# ProDoc_v3.net
KiCad netlist of a schematic drawn in EasyEDA Pro
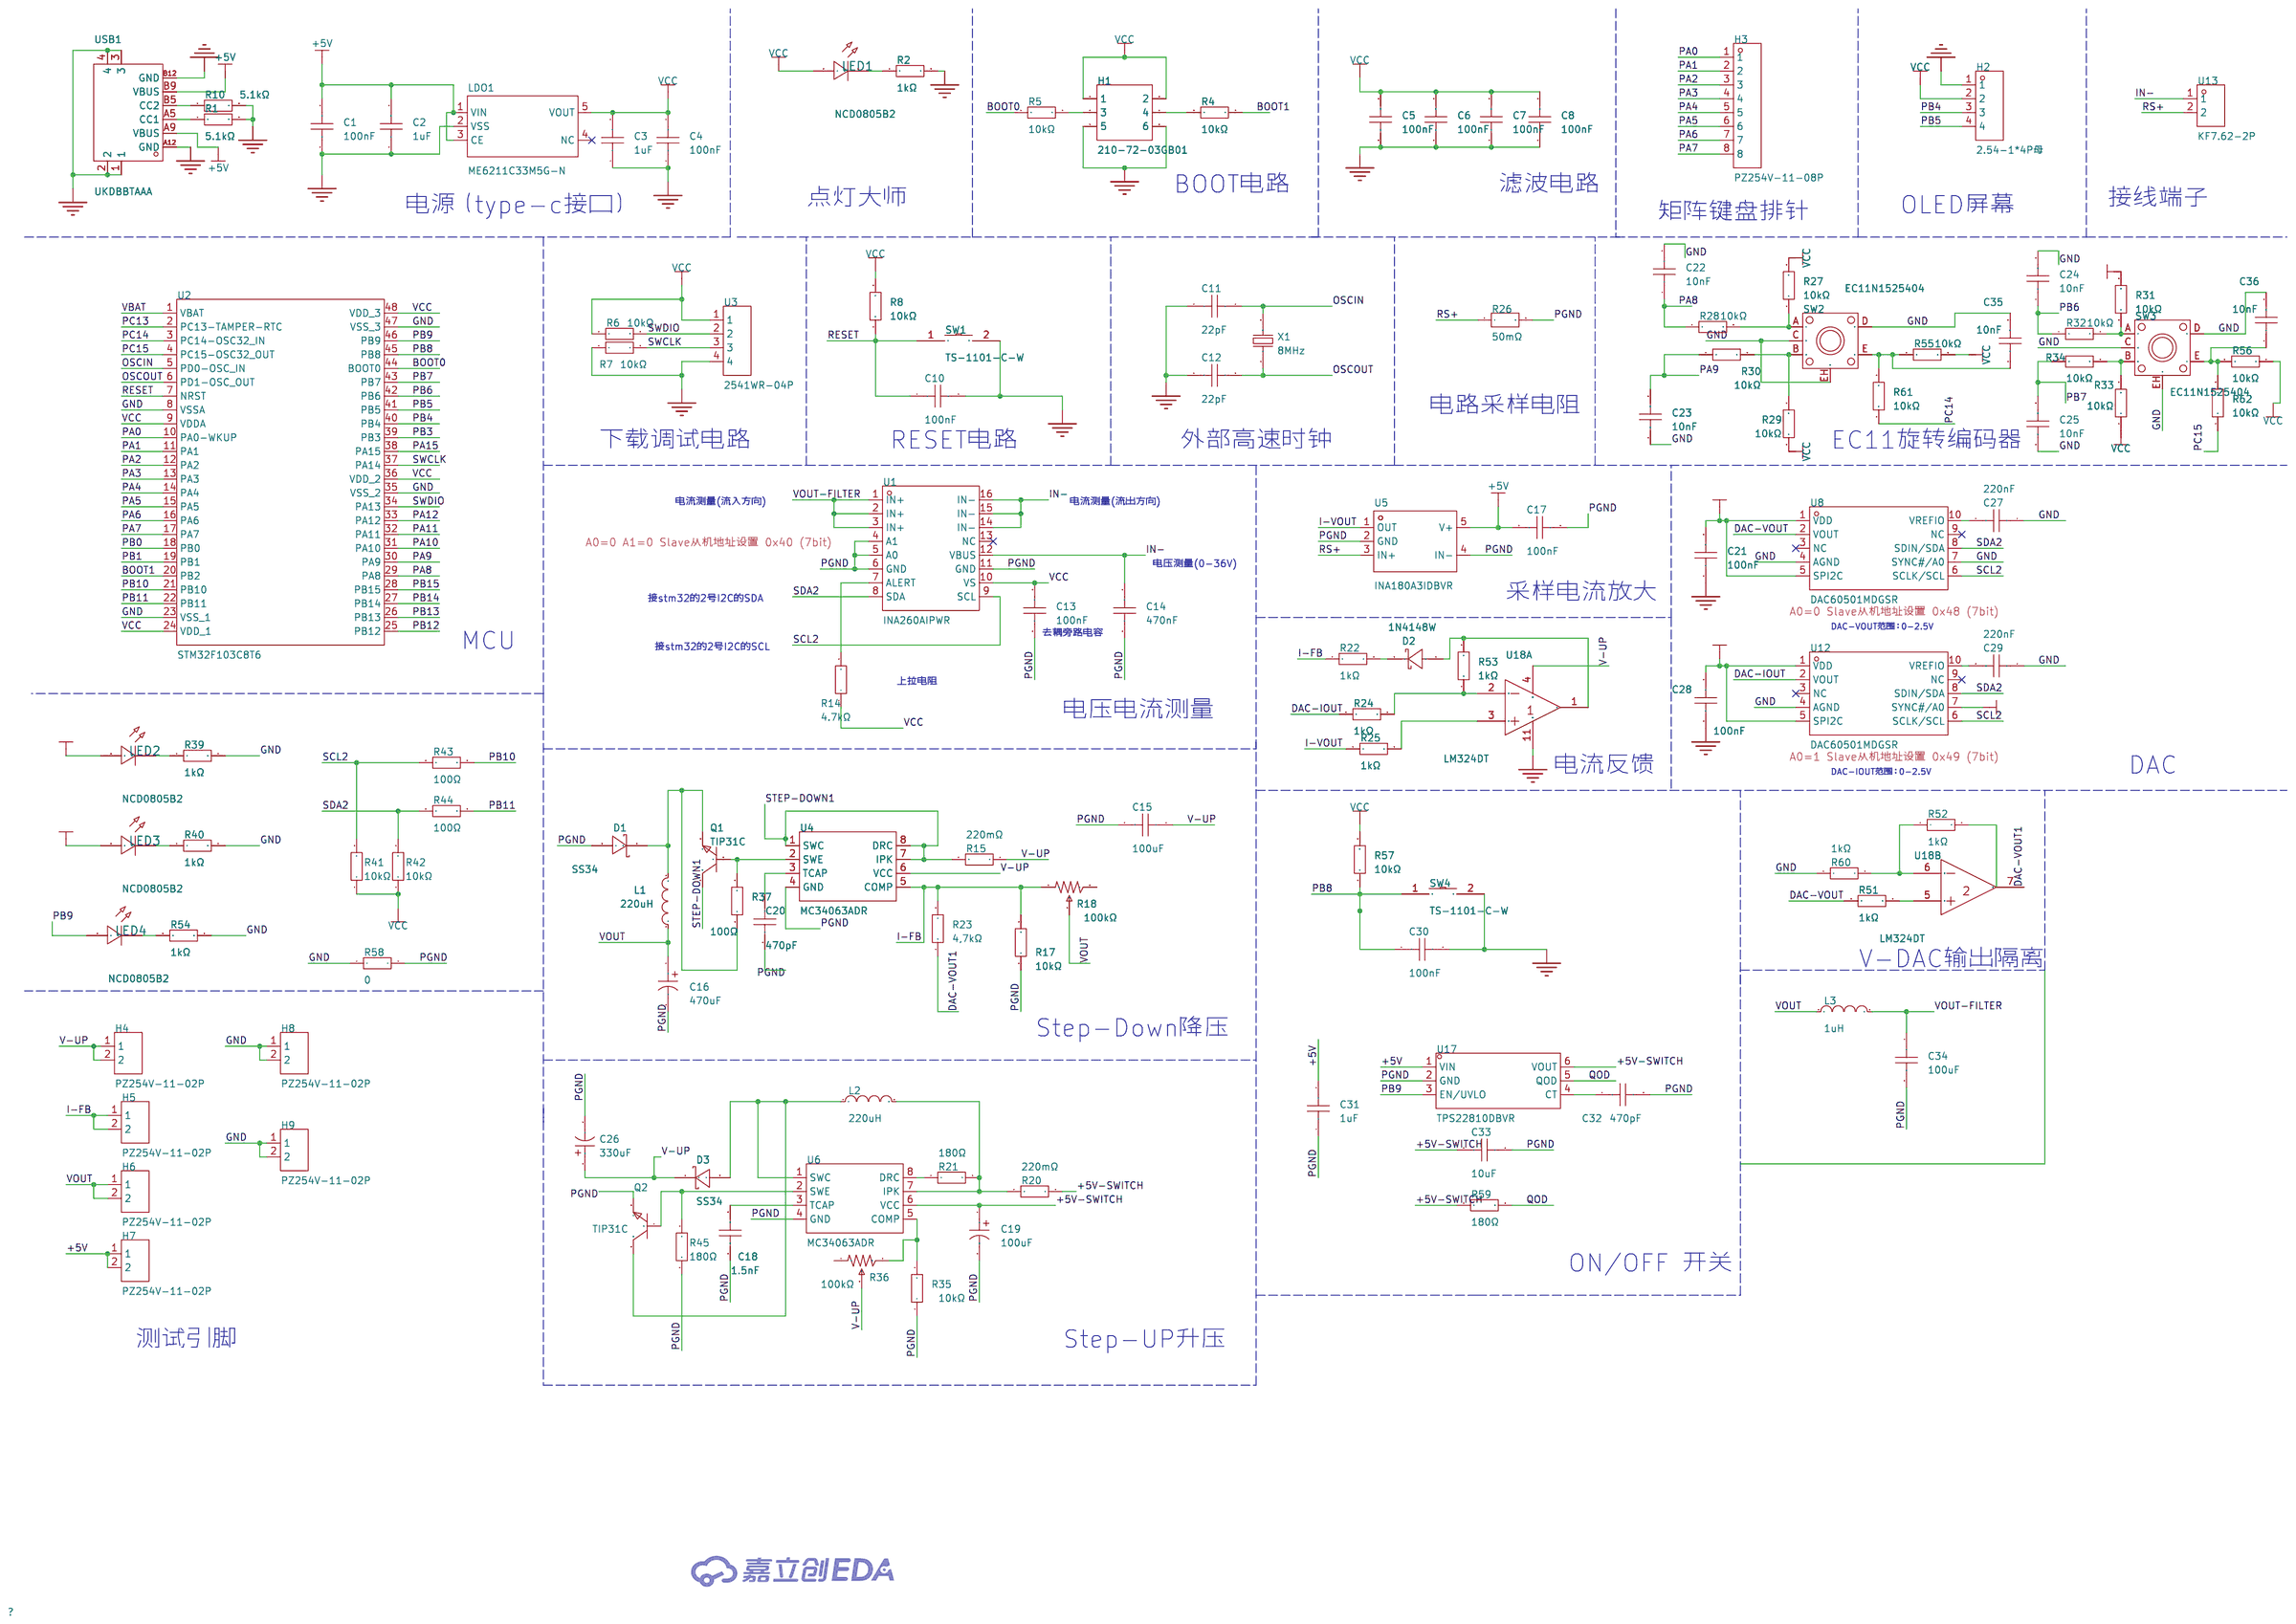
[diagram p0: schematic sheet]

(export (version "E")
  (design (tool "Eeschema 10.0.6"))
  (components
    (comp (ref "C1")
      (value "100nF")
      (fields (field (name "Manufacturer Part") "0805B104K500NT") (field (name "Manufacturer") "FH(风华)"))
      (libsource (lib "easyedapro") (part "Capacitance"))
    )
    (comp (ref "C2")
      (value "1uF")
      (fields
        (field (name "Manufacturer Part") "CL21B105KBFNNNE")
        (field (name "Manufacturer") "SAMSUNG(三星)")
      )
      (libsource (lib "easyedapro") (part "Capacitance"))
    )
    (comp (ref "C3")
      (value "1uF")
      (fields
        (field (name "Manufacturer Part") "CL21B105KBFNNNE")
        (field (name "Manufacturer") "SAMSUNG(三星)")
      )
      (libsource (lib "easyedapro") (part "Capacitance"))
    )
    (comp (ref "C4")
      (value "100nF")
      (fields (field (name "Manufacturer Part") "0805B104K500NT") (field (name "Manufacturer") "FH(风华)"))
      (libsource (lib "easyedapro") (part "Capacitance"))
    )
    (comp (ref "C5")
      (value "100nF")
      (fields (field (name "Manufacturer Part") "0805B104K500NT") (field (name "Manufacturer") "FH(风华)"))
      (libsource (lib "easyedapro") (part "Capacitance"))
    )
    (comp (ref "C6")
      (value "100nF")
      (fields (field (name "Manufacturer Part") "0805B104K500NT") (field (name "Manufacturer") "FH(风华)"))
      (libsource (lib "easyedapro") (part "Capacitance"))
    )
    (comp (ref "C7")
      (value "100nF")
      (fields (field (name "Manufacturer Part") "0805B104K500NT") (field (name "Manufacturer") "FH(风华)"))
      (libsource (lib "easyedapro") (part "Capacitance"))
    )
    (comp (ref "C8")
      (value "100nF")
      (fields (field (name "Manufacturer Part") "0805B104K500NT") (field (name "Manufacturer") "FH(风华)"))
      (libsource (lib "easyedapro") (part "Capacitance"))
    )
    (comp (ref "C10")
      (value "100nF")
      (fields (field (name "Manufacturer Part") "0805B104K500NT") (field (name "Manufacturer") "FH(风华)"))
      (libsource (lib "easyedapro") (part "Capacitance"))
    )
    (comp (ref "C11")
      (value "22pF")
      (fields (field (name "Manufacturer Part") "0805CG220J500NT") (field (name "Manufacturer") "FH(风华)"))
      (libsource (lib "easyedapro") (part "Capacitance"))
    )
    (comp (ref "C12")
      (value "22pF")
      (fields (field (name "Manufacturer Part") "0805CG220J500NT") (field (name "Manufacturer") "FH(风华)"))
      (libsource (lib "easyedapro") (part "Capacitance"))
    )
    (comp (ref "C13")
      (value "100nF")
      (fields (field (name "Manufacturer Part") "0805B104K500NT") (field (name "Manufacturer") "FH(风华)"))
      (libsource (lib "easyedapro") (part "Capacitance"))
    )
    (comp (ref "C14")
      (value "470nF")
      (fields (field (name "Manufacturer Part") "0805B474K500NT") (field (name "Manufacturer") "FH(风华)"))
      (libsource (lib "easyedapro") (part "Capacitance"))
    )
    (comp (ref "C15")
      (value "100uF")
      (fields (field (name "Manufacturer Part") "MA35V100M6X8") (field (name "Manufacturer") "JIERR(捷而瑞)"))
      (libsource (lib "easyedapro") (part "Capacitance"))
    )
    (comp (ref "C16")
      (value "470uF")
      (fields (field (name "Manufacturer Part") "MA25V470M8x10") (field (name "Manufacturer") "JIERR(捷而瑞)"))
      (libsource (lib "easyedapro") (part "JVJ25V470M8X10"))
    )
    (comp (ref "C17")
      (value "100nF")
      (fields (field (name "Manufacturer Part") "0805B104K500NT") (field (name "Manufacturer") "FH(风华)"))
      (libsource (lib "easyedapro") (part "Capacitance"))
    )
    (comp (ref "C18")
      (value "1.5nF")
      (fields (field (name "Manufacturer Part") "0805B152K500NT") (field (name "Manufacturer") "FH(风华)"))
      (libsource (lib "easyedapro") (part "Capacitance"))
    )
    (comp (ref "C19")
      (value "100uF")
      (fields (field (name "Manufacturer Part") "MA35V100M6X8") (field (name "Manufacturer") "JIERR(捷而瑞)"))
      (libsource (lib "easyedapro") (part "JVJ25V100M6X5"))
    )
    (comp (ref "C20")
      (value "470pF")
      (fields (field (name "Manufacturer Part") "0805B471K500NT") (field (name "Manufacturer") "FH(风华)"))
      (libsource (lib "easyedapro") (part "Capacitance"))
    )
    (comp (ref "C21")
      (value "100nF")
      (fields (field (name "Manufacturer Part") "0805B104K500NT") (field (name "Manufacturer") "FH(风华)"))
      (libsource (lib "easyedapro") (part "Capacitance"))
    )
    (comp (ref "C22")
      (value "10nF")
      (fields (field (name "Manufacturer Part") "0805B103K500NT") (field (name "Manufacturer") "FH(风华)"))
      (libsource (lib "easyedapro") (part "Capacitance"))
    )
    (comp (ref "C23")
      (value "10nF")
      (fields (field (name "Manufacturer Part") "0805B103K500NT") (field (name "Manufacturer") "FH(风华)"))
      (libsource (lib "easyedapro") (part "Capacitance"))
    )
    (comp (ref "C24")
      (value "10nF")
      (fields (field (name "Manufacturer Part") "0805B103K500NT") (field (name "Manufacturer") "FH(风华)"))
      (libsource (lib "easyedapro") (part "Capacitance"))
    )
    (comp (ref "C25")
      (value "10nF")
      (fields (field (name "Manufacturer Part") "0805B103K500NT") (field (name "Manufacturer") "FH(风华)"))
      (libsource (lib "easyedapro") (part "Capacitance"))
    )
    (comp (ref "C26")
      (value "330uF")
      (fields (field (name "Manufacturer Part") "MA35V330M10x10") (field (name "Manufacturer") "JIERR(捷而瑞)"))
      (libsource (lib "easyedapro") (part "JVJ25V470M8X10"))
    )
    (comp (ref "C27")
      (value "220nF")
      (fields (field (name "Manufacturer Part") "0805B224K500NT") (field (name "Manufacturer") "FH(风华)"))
      (libsource (lib "easyedapro") (part "Capacitance"))
    )
    (comp (ref "C28")
      (value "100nF")
      (fields (field (name "Manufacturer Part") "0805B104K500NT") (field (name "Manufacturer") "FH(风华)"))
      (libsource (lib "easyedapro") (part "Capacitance"))
    )
    (comp (ref "C29")
      (value "220nF")
      (fields (field (name "Manufacturer Part") "0805B224K500NT") (field (name "Manufacturer") "FH(风华)"))
      (libsource (lib "easyedapro") (part "Capacitance"))
    )
    (comp (ref "C30")
      (value "100nF")
      (fields (field (name "Manufacturer Part") "0805B104K500NT") (field (name "Manufacturer") "FH(风华)"))
      (libsource (lib "easyedapro") (part "Capacitance"))
    )
    (comp (ref "C31")
      (value "1uF")
      (fields
        (field (name "Manufacturer Part") "CL21B105KBFNNNE")
        (field (name "Manufacturer") "SAMSUNG(三星)")
      )
      (libsource (lib "easyedapro") (part "Capacitance"))
    )
    (comp (ref "C32")
      (value "470pF")
      (fields (field (name "Manufacturer Part") "0805B471K500NT") (field (name "Manufacturer") "FH(风华)"))
      (libsource (lib "easyedapro") (part "Capacitance"))
    )
    (comp (ref "C33")
      (value "10uF")
      (fields
        (field (name "Manufacturer Part") "CL21A106KAYNNNE")
        (field (name "Manufacturer") "SAMSUNG(三星)")
      )
      (libsource (lib "easyedapro") (part "Capacitance"))
    )
    (comp (ref "C34")
      (value "100uF")
      (fields (field (name "Manufacturer Part") "MA35V100M6X8") (field (name "Manufacturer") "JIERR(捷而瑞)"))
      (libsource (lib "easyedapro") (part "Capacitance"))
    )
    (comp (ref "C35")
      (value "10nF")
      (fields (field (name "Manufacturer Part") "0805B103K500NT") (field (name "Manufacturer") "FH(风华)"))
      (libsource (lib "easyedapro") (part "Capacitance"))
    )
    (comp (ref "C36")
      (value "10nF")
      (fields (field (name "Manufacturer Part") "0805B103K500NT") (field (name "Manufacturer") "FH(风华)"))
      (libsource (lib "easyedapro") (part "Capacitance"))
    )
    (comp (ref "D1")
      (value "SS34")
      (fields (field (name "Manufacturer") "R+O(宏嘉诚)"))
      (libsource (lib "easyedapro") (part "1N5819WS"))
    )
    (comp (ref "D2")
      (value "1N4148W")
      (footprint "easyedapro:SOD-123_L2.7-W1.6-LS3.7-FD")
      (description "二极管配置:独立式;正向压降(Vf):1.25V@150mA;直流反向耐压(Vr):100V;整流电流:150mA;反向恢复时间(Trr):4ns;")
      (fields (field (name "Manufacturer") "R+O(宏嘉诚)"))
      (libsource (lib "easyedapro") (part "1N4148W_C7420318"))
    )
    (comp (ref "D3")
      (value "SS34")
      (fields (field (name "Manufacturer") "R+O(宏嘉诚)"))
      (libsource (lib "easyedapro") (part "1N5819WS"))
    )
    (comp (ref "H1")
      (value "210-72-03GB01")
      (fields (field (name "Manufacturer") "PINREX(频锐科技)"))
      (libsource (lib "easyedapro") (part "HDR-M-2.54_2x3"))
    )
    (comp (ref "H2")
      (value "2.54-1*4P母")
      (footprint "easyedapro:HDR-TH_4P-P2.54-V-F")
      (fields (field (name "Manufacturer") "BOOMELE(博穆精密)"))
      (libsource (lib "easyedapro") (part "2.54-1*4P母"))
    )
    (comp (ref "H3")
      (value "PZ254V-11-08P")
      (footprint "easyedapro:HDR-TH_8P-P2.54-V-M")
      (fields (field (name "Manufacturer") "XFCN(兴飞)"))
      (libsource (lib "easyedapro") (part "PZ254V-11-08P"))
    )
    (comp (ref "H4")
      (value "PZ254V-11-02P")
      (footprint "easyedapro:HDR-TH_2P-P2.54-V-M")
      (fields (field (name "Manufacturer") "XFCN(兴飞)"))
      (libsource (lib "easyedapro") (part "PZ254V-11-02P"))
    )
    (comp (ref "H5")
      (value "PZ254V-11-02P")
      (footprint "easyedapro:HDR-TH_2P-P2.54-V-M")
      (fields (field (name "Manufacturer") "XFCN(兴飞)"))
      (libsource (lib "easyedapro") (part "PZ254V-11-02P"))
    )
    (comp (ref "H6")
      (value "PZ254V-11-02P")
      (footprint "easyedapro:HDR-TH_2P-P2.54-V-M")
      (fields (field (name "Manufacturer") "XFCN(兴飞)"))
      (libsource (lib "easyedapro") (part "PZ254V-11-02P"))
    )
    (comp (ref "H7")
      (value "PZ254V-11-02P")
      (footprint "easyedapro:HDR-TH_2P-P2.54-V-M")
      (fields (field (name "Manufacturer") "XFCN(兴飞)"))
      (libsource (lib "easyedapro") (part "PZ254V-11-02P"))
    )
    (comp (ref "H8")
      (value "PZ254V-11-02P")
      (footprint "easyedapro:HDR-TH_2P-P2.54-V-M")
      (fields (field (name "Manufacturer") "XFCN(兴飞)"))
      (libsource (lib "easyedapro") (part "PZ254V-11-02P"))
    )
    (comp (ref "H9")
      (value "PZ254V-11-02P")
      (footprint "easyedapro:HDR-TH_2P-P2.54-V-M")
      (fields (field (name "Manufacturer") "XFCN(兴飞)"))
      (libsource (lib "easyedapro") (part "PZ254V-11-02P"))
    )
    (comp (ref "L1")
      (value "220uH")
      (fields (field (name "Manufacturer Part") "SMDRI127-221MT") (field (name "Manufacturer") "SXN(顺翔诺)"))
      (libsource (lib "easyedapro") (part "FNR5040S221MT"))
    )
    (comp (ref "L2")
      (value "220uH")
      (fields (field (name "Manufacturer Part") "SMDRI127-221MT") (field (name "Manufacturer") "SXN(顺翔诺)"))
      (libsource (lib "easyedapro") (part "FNR5040S221MT"))
    )
    (comp (ref "L3")
      (value "1uH")
      (fields (field (name "Manufacturer Part") "FXL0630-1R0-M") (field (name "Manufacturer") "cjiang(长江微电)"))
      (libsource (lib "easyedapro") (part "FXL0420-1R0-M"))
    )
    (comp (ref "LDO1")
      (value "ME6211C33M5G-N")
      (footprint "easyedapro:SOT-23-5_L3.0-W1.7-P0.95-LS2.8-BL")
      (description "输出类型:固定;工作电压:6V;输出电压:3.3V;输出电流:500mA;电源纹波抑制比(PSRR):70dB@(1kHz);输出极性:正极;")
      (fields (field (name "Manufacturer") "MICRONE(南京微盟)"))
      (libsource (lib "easyedapro") (part "ME6211C33M5G-N"))
    )
    (comp (ref "LED1")
      (value "NCD0805B2")
      (fields (field (name "Manufacturer") "国星光电"))
      (libsource (lib "easyedapro") (part "LED_R"))
    )
    (comp (ref "LED2")
      (value "NCD0805B2")
      (fields (field (name "Manufacturer") "国星光电"))
      (libsource (lib "easyedapro") (part "LED_R"))
    )
    (comp (ref "LED3")
      (value "NCD0805B2")
      (fields (field (name "Manufacturer") "国星光电"))
      (libsource (lib "easyedapro") (part "LED_R"))
    )
    (comp (ref "LED4")
      (value "NCD0805B2")
      (fields (field (name "Manufacturer") "国星光电"))
      (libsource (lib "easyedapro") (part "LED_R"))
    )
    (comp (ref "Q1")
      (value "TIP31C")
      (footprint "easyedapro:TO-220-3_L10.0-W4.5-P2.54-L")
      (description "晶体管类型:NPN;集电极电流(Ic):3A;集射极击穿电压(Vceo):100V;耗散功率(Pd):40W;直流电流增益(hFE):50@3A,4V;")
      (fields (field (name "Manufacturer") "JSMSEMI(杰盛微)"))
      (libsource (lib "easyedapro") (part "TIP31C_C963401"))
    )
    (comp (ref "Q2")
      (value "TIP31C")
      (footprint "easyedapro:TO-220-3_L10.0-W4.5-P2.54-L")
      (description "晶体管类型:NPN;集电极电流(Ic):3A;集射极击穿电压(Vceo):100V;耗散功率(Pd):40W;直流电流增益(hFE):50@3A,4V;")
      (fields (field (name "Manufacturer") "JSMSEMI(杰盛微)"))
      (libsource (lib "easyedapro") (part "TIP31C_C963401"))
    )
    (comp (ref "R1")
      (value "5.1kΩ")
      (footprint "easyedapro:R0805")
      (fields
        (field (name "Manufacturer Part") "0805W8F5101T5E")
        (field (name "Manufacturer") "UNI-ROYAL(厚声)")
      )
      (libsource (lib "easyedapro") (part "电阻"))
    )
    (comp (ref "R2")
      (value "1kΩ")
      (footprint "easyedapro:R0805")
      (fields
        (field (name "Manufacturer Part") "0805W8F1001T5E")
        (field (name "Manufacturer") "UNI-ROYAL(厚声)")
      )
      (libsource (lib "easyedapro") (part "电阻"))
    )
    (comp (ref "R4")
      (value "10kΩ")
      (footprint "easyedapro:R0805")
      (fields
        (field (name "Manufacturer Part") "0805W8F1002T5E")
        (field (name "Manufacturer") "UNI-ROYAL(厚声)")
      )
      (libsource (lib "easyedapro") (part "电阻"))
    )
    (comp (ref "R5")
      (value "10kΩ")
      (footprint "easyedapro:R0805")
      (fields
        (field (name "Manufacturer Part") "0805W8F1002T5E")
        (field (name "Manufacturer") "UNI-ROYAL(厚声)")
      )
      (libsource (lib "easyedapro") (part "电阻"))
    )
    (comp (ref "R6")
      (value "10kΩ")
      (footprint "easyedapro:R0805")
      (fields
        (field (name "Manufacturer Part") "0805W8F1002T5E")
        (field (name "Manufacturer") "UNI-ROYAL(厚声)")
      )
      (libsource (lib "easyedapro") (part "电阻"))
    )
    (comp (ref "R7")
      (value "10kΩ")
      (footprint "easyedapro:R0805")
      (fields
        (field (name "Manufacturer Part") "0805W8F1002T5E")
        (field (name "Manufacturer") "UNI-ROYAL(厚声)")
      )
      (libsource (lib "easyedapro") (part "电阻"))
    )
    (comp (ref "R8")
      (value "10kΩ")
      (footprint "easyedapro:R0805")
      (fields
        (field (name "Manufacturer Part") "0805W8F1002T5E")
        (field (name "Manufacturer") "UNI-ROYAL(厚声)")
      )
      (libsource (lib "easyedapro") (part "电阻"))
    )
    (comp (ref "R10")
      (value "5.1kΩ")
      (footprint "easyedapro:R0805")
      (fields
        (field (name "Manufacturer Part") "0805W8F5101T5E")
        (field (name "Manufacturer") "UNI-ROYAL(厚声)")
      )
      (libsource (lib "easyedapro") (part "电阻"))
    )
    (comp (ref "R14")
      (value "4.7kΩ")
      (footprint "easyedapro:R0805")
      (fields
        (field (name "Manufacturer Part") "0805W8F4701T5E")
        (field (name "Manufacturer") "UNI-ROYAL(厚声)")
      )
      (libsource (lib "easyedapro") (part "电阻"))
    )
    (comp (ref "R15")
      (value "220mΩ")
      (footprint "easyedapro:R0805")
      (fields (field (name "Manufacturer Part") "FRL1206FR220TS") (field (name "Manufacturer") "FOJAN(富捷)"))
      (libsource (lib "easyedapro") (part "电阻"))
    )
    (comp (ref "R17")
      (value "10kΩ")
      (footprint "easyedapro:R0805")
      (fields
        (field (name "Manufacturer Part") "0805W8F1002T5E")
        (field (name "Manufacturer") "UNI-ROYAL(厚声)")
      )
      (libsource (lib "easyedapro") (part "电阻"))
    )
    (comp (ref "R18")
      (value "100kΩ")
      (fields (field (name "Manufacturer Part") "3296W-1-104LF") (field (name "Manufacturer") "BOURNS"))
      (libsource (lib "easyedapro") (part "3296W-1-103_C48997937"))
    )
    (comp (ref "R20")
      (value "220mΩ")
      (footprint "easyedapro:R0805")
      (fields (field (name "Manufacturer Part") "FRL1206FR220TS") (field (name "Manufacturer") "FOJAN(富捷)"))
      (libsource (lib "easyedapro") (part "电阻"))
    )
    (comp (ref "R21")
      (value "180Ω")
      (footprint "easyedapro:R0805")
      (fields
        (field (name "Manufacturer Part") "0805W8F1800T5E")
        (field (name "Manufacturer") "UNI-ROYAL(厚声)")
      )
      (libsource (lib "easyedapro") (part "电阻"))
    )
    (comp (ref "R22")
      (value "1kΩ")
      (footprint "easyedapro:R0805")
      (fields
        (field (name "Manufacturer Part") "0805W8F1001T5E")
        (field (name "Manufacturer") "UNI-ROYAL(厚声)")
      )
      (libsource (lib "easyedapro") (part "电阻"))
    )
    (comp (ref "R23")
      (value "4,7kΩ")
      (footprint "easyedapro:R0805")
      (fields
        (field (name "Manufacturer Part") "0805W8F1002T5E")
        (field (name "Manufacturer") "UNI-ROYAL(厚声)")
      )
      (libsource (lib "easyedapro") (part "电阻"))
    )
    (comp (ref "R24")
      (value "1kΩ")
      (footprint "easyedapro:R0805")
      (fields
        (field (name "Manufacturer Part") "0805W8F1001T5E")
        (field (name "Manufacturer") "UNI-ROYAL(厚声)")
      )
      (libsource (lib "easyedapro") (part "电阻"))
    )
    (comp (ref "R25")
      (value "1kΩ")
      (footprint "easyedapro:R0805")
      (fields
        (field (name "Manufacturer Part") "0805W8F1001T5E")
        (field (name "Manufacturer") "UNI-ROYAL(厚声)")
      )
      (libsource (lib "easyedapro") (part "电阻"))
    )
    (comp (ref "R26")
      (value "50mΩ")
      (footprint "easyedapro:R1206")
      (description "电阻类型:采样电阻；合金电阻;阻值:50mΩ;精度:±1%;功率:1W;温度系数:±50ppm/°C;")
      (fields (field (name "Manufacturer Part") "RE1206F1R050") (field (name "Manufacturer") "JIERR(捷而瑞)"))
      (libsource (lib "easyedapro") (part "RE1206F1R050"))
    )
    (comp (ref "R27")
      (value "10kΩ")
      (footprint "easyedapro:R0805")
      (fields
        (field (name "Manufacturer Part") "0805W8F1002T5E")
        (field (name "Manufacturer") "UNI-ROYAL(厚声)")
      )
      (libsource (lib "easyedapro") (part "电阻"))
    )
    (comp (ref "R28")
      (value "10kΩ")
      (footprint "easyedapro:R0805")
      (fields
        (field (name "Manufacturer Part") "0805W8F1002T5E")
        (field (name "Manufacturer") "UNI-ROYAL(厚声)")
      )
      (libsource (lib "easyedapro") (part "电阻"))
    )
    (comp (ref "R29")
      (value "10kΩ")
      (footprint "easyedapro:R0805")
      (fields
        (field (name "Manufacturer Part") "0805W8F1002T5E")
        (field (name "Manufacturer") "UNI-ROYAL(厚声)")
      )
      (libsource (lib "easyedapro") (part "电阻"))
    )
    (comp (ref "R30")
      (value "10kΩ")
      (footprint "easyedapro:R0805")
      (fields
        (field (name "Manufacturer Part") "0805W8F1002T5E")
        (field (name "Manufacturer") "UNI-ROYAL(厚声)")
      )
      (libsource (lib "easyedapro") (part "电阻"))
    )
    (comp (ref "R31")
      (value "10kΩ")
      (footprint "easyedapro:R0805")
      (fields
        (field (name "Manufacturer Part") "0805W8F1002T5E")
        (field (name "Manufacturer") "UNI-ROYAL(厚声)")
      )
      (libsource (lib "easyedapro") (part "电阻"))
    )
    (comp (ref "R32")
      (value "10kΩ")
      (footprint "easyedapro:R0805")
      (fields
        (field (name "Manufacturer Part") "0805W8F1002T5E")
        (field (name "Manufacturer") "UNI-ROYAL(厚声)")
      )
      (libsource (lib "easyedapro") (part "电阻"))
    )
    (comp (ref "R33")
      (value "10kΩ")
      (footprint "easyedapro:R0805")
      (fields
        (field (name "Manufacturer Part") "0805W8F1002T5E")
        (field (name "Manufacturer") "UNI-ROYAL(厚声)")
      )
      (libsource (lib "easyedapro") (part "电阻"))
    )
    (comp (ref "R34")
      (value "10kΩ")
      (footprint "easyedapro:R0805")
      (fields
        (field (name "Manufacturer Part") "0805W8F1002T5E")
        (field (name "Manufacturer") "UNI-ROYAL(厚声)")
      )
      (libsource (lib "easyedapro") (part "电阻"))
    )
    (comp (ref "R35")
      (value "10kΩ")
      (footprint "easyedapro:R0805")
      (fields
        (field (name "Manufacturer Part") "0805W8F1002T5E")
        (field (name "Manufacturer") "UNI-ROYAL(厚声)")
      )
      (libsource (lib "easyedapro") (part "电阻"))
    )
    (comp (ref "R36")
      (value "100kΩ")
      (fields (field (name "Manufacturer Part") "3296W-1-104") (field (name "Manufacturer") "JIERR(捷而瑞)"))
      (libsource (lib "easyedapro") (part "3296W-1-103_C48997937"))
    )
    (comp (ref "R37")
      (value "100Ω")
      (footprint "easyedapro:R0805")
      (fields
        (field (name "Manufacturer Part") "0805W8F1000T5E")
        (field (name "Manufacturer") "UNI-ROYAL(厚声)")
      )
      (libsource (lib "easyedapro") (part "电阻"))
    )
    (comp (ref "R39")
      (value "1kΩ")
      (footprint "easyedapro:R0805")
      (fields
        (field (name "Manufacturer Part") "0805W8F1001T5E")
        (field (name "Manufacturer") "UNI-ROYAL(厚声)")
      )
      (libsource (lib "easyedapro") (part "电阻"))
    )
    (comp (ref "R40")
      (value "1kΩ")
      (footprint "easyedapro:R0805")
      (fields
        (field (name "Manufacturer Part") "0805W8F1001T5E")
        (field (name "Manufacturer") "UNI-ROYAL(厚声)")
      )
      (libsource (lib "easyedapro") (part "电阻"))
    )
    (comp (ref "R41")
      (value "10kΩ")
      (footprint "easyedapro:R0805")
      (fields
        (field (name "Manufacturer Part") "0805W8F1002T5E")
        (field (name "Manufacturer") "UNI-ROYAL(厚声)")
      )
      (libsource (lib "easyedapro") (part "电阻"))
    )
    (comp (ref "R42")
      (value "10kΩ")
      (footprint "easyedapro:R0805")
      (fields
        (field (name "Manufacturer Part") "0805W8F1002T5E")
        (field (name "Manufacturer") "UNI-ROYAL(厚声)")
      )
      (libsource (lib "easyedapro") (part "电阻"))
    )
    (comp (ref "R43")
      (value "100Ω")
      (footprint "easyedapro:R0805")
      (fields
        (field (name "Manufacturer Part") "0805W8F1000T5E")
        (field (name "Manufacturer") "UNI-ROYAL(厚声)")
      )
      (libsource (lib "easyedapro") (part "电阻"))
    )
    (comp (ref "R44")
      (value "100Ω")
      (footprint "easyedapro:R0805")
      (fields
        (field (name "Manufacturer Part") "0805W8F1000T5E")
        (field (name "Manufacturer") "UNI-ROYAL(厚声)")
      )
      (libsource (lib "easyedapro") (part "电阻"))
    )
    (comp (ref "R45")
      (value "180Ω")
      (footprint "easyedapro:R0805")
      (fields
        (field (name "Manufacturer Part") "0805W8F1800T5E")
        (field (name "Manufacturer") "UNI-ROYAL(厚声)")
      )
      (libsource (lib "easyedapro") (part "电阻"))
    )
    (comp (ref "R51")
      (value "1kΩ")
      (footprint "easyedapro:R0805")
      (fields
        (field (name "Manufacturer Part") "0805W8F1001T5E")
        (field (name "Manufacturer") "UNI-ROYAL(厚声)")
      )
      (libsource (lib "easyedapro") (part "电阻"))
    )
    (comp (ref "R52")
      (value "1kΩ")
      (footprint "easyedapro:R0805")
      (fields
        (field (name "Manufacturer Part") "0805W8F1001T5E")
        (field (name "Manufacturer") "UNI-ROYAL(厚声)")
      )
      (libsource (lib "easyedapro") (part "电阻"))
    )
    (comp (ref "R53")
      (value "1kΩ")
      (footprint "easyedapro:R0805")
      (fields
        (field (name "Manufacturer Part") "0805W8F1001T5E")
        (field (name "Manufacturer") "UNI-ROYAL(厚声)")
      )
      (libsource (lib "easyedapro") (part "电阻"))
    )
    (comp (ref "R54")
      (value "1kΩ")
      (footprint "easyedapro:R0805")
      (fields
        (field (name "Manufacturer Part") "0805W8F1001T5E")
        (field (name "Manufacturer") "UNI-ROYAL(厚声)")
      )
      (libsource (lib "easyedapro") (part "电阻"))
    )
    (comp (ref "R55")
      (value "10kΩ")
      (footprint "easyedapro:R0805")
      (fields
        (field (name "Manufacturer Part") "0805W8F1002T5E")
        (field (name "Manufacturer") "UNI-ROYAL(厚声)")
      )
      (libsource (lib "easyedapro") (part "电阻"))
    )
    (comp (ref "R56")
      (value "10kΩ")
      (footprint "easyedapro:R0805")
      (fields
        (field (name "Manufacturer Part") "0805W8F1002T5E")
        (field (name "Manufacturer") "UNI-ROYAL(厚声)")
      )
      (libsource (lib "easyedapro") (part "电阻"))
    )
    (comp (ref "R57")
      (value "10kΩ")
      (footprint "easyedapro:R0805")
      (fields
        (field (name "Manufacturer Part") "0805W8F1002T5E")
        (field (name "Manufacturer") "UNI-ROYAL(厚声)")
      )
      (libsource (lib "easyedapro") (part "电阻"))
    )
    (comp (ref "R58") (value "0") (footprint "easyedapro:R0805") (libsource (lib "easyedapro") (part "电阻")))
    (comp (ref "R59")
      (value "180Ω")
      (footprint "easyedapro:R0805")
      (fields
        (field (name "Manufacturer Part") "0805W8F1800T5E")
        (field (name "Manufacturer") "UNI-ROYAL(厚声)")
      )
      (libsource (lib "easyedapro") (part "电阻"))
    )
    (comp (ref "R60")
      (value "1kΩ")
      (footprint "easyedapro:R0805")
      (fields
        (field (name "Manufacturer Part") "0805W8F1001T5E")
        (field (name "Manufacturer") "UNI-ROYAL(厚声)")
      )
      (libsource (lib "easyedapro") (part "电阻"))
    )
    (comp (ref "R61")
      (value "10kΩ")
      (footprint "easyedapro:R0805")
      (fields
        (field (name "Manufacturer Part") "0805W8F1002T5E")
        (field (name "Manufacturer") "UNI-ROYAL(厚声)")
      )
      (libsource (lib "easyedapro") (part "电阻"))
    )
    (comp (ref "R62")
      (value "10kΩ")
      (footprint "easyedapro:R0805")
      (fields
        (field (name "Manufacturer Part") "0805W8F1002T5E")
        (field (name "Manufacturer") "UNI-ROYAL(厚声)")
      )
      (libsource (lib "easyedapro") (part "电阻"))
    )
    (comp (ref "SW1")
      (value "TS-1101-C-W")
      (footprint "easyedapro:SW-SMD_L6.0-W3.3-LS8.0")
      (fields (field (name "Manufacturer") "XKB Connectivity(中国星坤)"))
      (libsource (lib "easyedapro") (part "TS-1101-C-W"))
    )
    (comp (ref "SW2")
      (value "EC11N1525404")
      (footprint "easyedapro:SW-TH_EC11NXXXX")
      (fields (field (name "Manufacturer") "ALPSALPINE(阿尔卑斯阿尔派)"))
      (libsource (lib "easyedapro") (part "EC11N1525404"))
    )
    (comp (ref "SW3")
      (value "EC11N1525404")
      (footprint "easyedapro:SW-TH_EC11NXXXX")
      (fields (field (name "Manufacturer") "ALPSALPINE(阿尔卑斯阿尔派)"))
      (libsource (lib "easyedapro") (part "EC11N1525404"))
    )
    (comp (ref "SW4")
      (value "TS-1101-C-W")
      (footprint "easyedapro:SW-SMD_L6.0-W3.3-LS8.0")
      (fields (field (name "Manufacturer") "XKB Connectivity(中国星坤)"))
      (libsource (lib "easyedapro") (part "TS-1101-C-W"))
    )
    (comp (ref "U1")
      (value "INA260AIPWR")
      (footprint "easyedapro:TSSOP-16_L5.0-W4.4-P0.65-LS6.4-BL-1")
      (description "INA260 具有集成分流电阻的 36V、16 位、精密 I2C 输出电流/电压/功率监控器")
      (fields (field (name "Manufacturer") "TI(德州仪器)"))
      (libsource (lib "easyedapro") (part "INA260AIPWR"))
    )
    (comp (ref "U2")
      (value "STM32F103C8T6")
      (footprint "easyedapro:LQFP-48_L7.0-W7.0-P0.50-LS9.0-BL")
      (description "CPU内核:ARM-M3;CPU最大主频:72MHz;应用领域:-;")
      (fields (field (name "Manufacturer") "ST(意法半导体)"))
      (libsource (lib "easyedapro") (part "STM32F103C8T6"))
    )
    (comp (ref "U3")
      (value "2541WR-04P")
      (footprint "easyedapro:HDR-TH_4P-P2.54-H-M-W10.4-N")
      (description "插针结构:1x4P;间距:2.54mm;圆针/方针:方针;安装方式:弯插;排数:单排;总PIN位数:4P;配合针长度:6mm;塑高:2.54mm;触头镀层:金;工作温度:-40°C~+105°C;")
      (fields (field (name "Manufacturer") "HanElectricity(瀚源)"))
      (libsource (lib "easyedapro") (part "2541WR-04P"))
    )
    (comp (ref "U4")
      (value "MC34063ADR")
      (footprint "easyedapro:SOIC-8_L4.9-W3.9-P1.27-LS6.0-BL")
      (description "功能类型:升压型；降压型;工作电压:3V~40V;输出电压:-;输出电流:1.5A;输出类型:可调;")
      (fields (field (name "Manufacturer") "TI(德州仪器)"))
      (libsource (lib "easyedapro") (part "MC34063ADR"))
    )
    (comp (ref "U5")
      (value "INA180A3IDBVR")
      (footprint "easyedapro:SOT-23-5_L3.0-W1.7-P0.95-LS2.8-BR")
      (description "放大器数:单路;共模电压:-200mV~26V;增益:100V/V;带宽:150kHz;")
      (fields (field (name "Manufacturer") "TI(德州仪器)"))
      (libsource (lib "easyedapro") (part "INA180A3IDBVR"))
    )
    (comp (ref "U6")
      (value "MC34063ADR")
      (footprint "easyedapro:SOIC-8_L4.9-W3.9-P1.27-LS6.0-BL")
      (description "功能类型:升压型；降压型;工作电压:3V~40V;输出电压:-;输出电流:1.5A;输出类型:可调;")
      (fields (field (name "Manufacturer") "TI(德州仪器)"))
      (libsource (lib "easyedapro") (part "MC34063ADR"))
    )
    (comp (ref "U8")
      (value "DAC60501MDGSR")
      (footprint "easyedapro:VSSOP-10_L3.0-W3.0-P0.50-LS4.9-BL")
      (description "分辨率:12位;接口类型:SPI；I2C;工作电压:2.7V~5.5V;稳定时间:5us;积分非线性:1LSB;")
      (fields (field (name "Manufacturer") "TI(德州仪器)"))
      (libsource (lib "easyedapro") (part "DAC60501MDGSR"))
    )
    (comp (ref "U12")
      (value "DAC60501MDGSR")
      (footprint "easyedapro:VSSOP-10_L3.0-W3.0-P0.50-LS4.9-BL")
      (description "分辨率:12位;接口类型:SPI；I2C;工作电压:2.7V~5.5V;稳定时间:5us;积分非线性:1LSB;")
      (fields (field (name "Manufacturer") "TI(德州仪器)"))
      (libsource (lib "easyedapro") (part "DAC60501MDGSR"))
    )
    (comp (ref "U13")
      (value "KF7.62-2P")
      (footprint "easyedapro:CONN-TH_KF7.62-2P")
      (fields (field (name "Manufacturer") "KEFA(科发)"))
      (libsource (lib "easyedapro") (part "KF7.62-2P"))
    )
    (comp (ref "U17")
      (value "TPS22810DBVR")
      (footprint "easyedapro:SOT-23-6_L2.9-W1.6-P0.95-LS2.8-BL")
      (description "类型:负载开关;通道数:1;输入控制逻辑:高电平有效;最大连续电流:2A;工作电压:2.7V~18V;导通电阻:79mΩ;")
      (fields (field (name "Manufacturer") "TI(德州仪器)"))
      (libsource (lib "easyedapro") (part "TPS22810DBVR"))
    )
    (comp (ref "U18")
      (value "LM324DT")
      (footprint "easyedapro:SOIC-14_L8.7-W3.9-P1.27-LS6.0-BL")
      (description "放大器数:四路;轨到轨:-;增益带宽积(GBP):1.3MHz;输入失调电压(Vos):5mV;压摆率(SR):20V/us;输入偏置电流(Ib):300nA;")
      (fields (field (name "Manufacturer") "ST(意法半导体)"))
      (libsource (lib "easyedapro") (part "LM324DT"))
    )
    (comp (ref "USB1")
      (value "UKDBBTAAA")
      (footprint "easyedapro:USB-C-SMD")
      (description "连接器类型:Type-C;协议标准:USB 3.1;公母:母;安装方式:卧贴;触点数量:6P;端口数量:1;额定电流 - 电源:3A;工作温度:-25°C~+85°C;")
      (fields (field (name "Manufacturer") "SAMZO(三佐)"))
      (libsource (lib "easyedapro") (part "UKDBBTAAA"))
    )
    (comp (ref "X1")
      (value "8MHz")
      (footprint "easyedapro:CRYSTAL-TH_L11.1-W4.7-P4.88")
      (description "晶振类型:直插晶振;频率:8MHz;常温频差:±10ppm;负载电容:20pF;频率稳定度:±30ppm;")
      (fields (field (name "Manufacturer Part") "YG8MLBBE2X") (field (name "Manufacturer") "YJX(雅晶鑫)"))
      (libsource (lib "easyedapro") (part "YG8MLBBE2X"))
    )
  )
  (nets
    (net (code "1") (name "+5V") (class "Default")
      (node (ref "C1") (pin "2") (pinfunction "2_2") (pintype "input"))
      (node (ref "C17") (pin "1") (pinfunction "1_1") (pintype "input"))
      (node (ref "C2") (pin "2") (pinfunction "2_2") (pintype "input"))
      (node (ref "C31") (pin "2") (pinfunction "2_2") (pintype "input"))
      (node (ref "H7") (pin "1") (pinfunction "1_1") (pintype "unspecified"))
      (node (ref "H7") (pin "2") (pinfunction "2_2") (pintype "unspecified"))
      (node (ref "LDO1") (pin "1") (pinfunction "VIN_1") (pintype "unspecified"))
      (node (ref "LDO1") (pin "3") (pinfunction "CE_3") (pintype "unspecified"))
      (node (ref "U17") (pin "1") (pinfunction "VIN_1") (pintype "unspecified"))
      (node (ref "U5") (pin "5") (pinfunction "V+_5") (pintype "unspecified"))
      (node (ref "USB1") (pin "A9") (pinfunction "VBUS_A9") (pintype "unspecified"))
      (node (ref "USB1") (pin "B9") (pinfunction "VBUS_B9") (pintype "unspecified"))
    )
    (net (code "2") (name "/+5V-SWITCH") (class "Default")
      (node (ref "C19") (pin "1") (pinfunction "1_1") (pintype "input"))
      (node (ref "C33") (pin "1") (pinfunction "1_1") (pintype "input"))
      (node (ref "R20") (pin "2") (pinfunction "2_2") (pintype "input"))
      (node (ref "R59") (pin "1") (pinfunction "1_1") (pintype "input"))
      (node (ref "U17") (pin "6") (pinfunction "VOUT_6") (pintype "unspecified"))
      (node (ref "U6") (pin "6") (pinfunction "VCC_6") (pintype "unspecified"))
    )
    (net (code "3") (name "/BOOT0") (class "Default")
      (node (ref "R5") (pin "1") (pinfunction "1_1") (pintype "input"))
      (node (ref "U2") (pin "44") (pinfunction "BOOT0_44") (pintype "unspecified"))
    )
    (net (code "4") (name "/BOOT1") (class "Default")
      (node (ref "R4") (pin "2") (pinfunction "2_2") (pintype "input"))
      (node (ref "U2") (pin "20") (pinfunction "PB2_20") (pintype "unspecified"))
    )
    (net (code "5") (name "/DAC-IOUT") (class "Default")
      (node (ref "R24") (pin "1") (pinfunction "1_1") (pintype "input"))
      (node (ref "U12") (pin "2") (pinfunction "VOUT_2") (pintype "unspecified"))
    )
    (net (code "6") (name "/DAC-VOUT") (class "Default")
      (node (ref "R51") (pin "1") (pinfunction "1_1") (pintype "input"))
      (node (ref "U8") (pin "2") (pinfunction "VOUT_2") (pintype "unspecified"))
    )
    (net (code "7") (name "/DAC-VOUT1") (class "Default")
      (node (ref "R23") (pin "1") (pinfunction "1_1") (pintype "input"))
      (node (ref "R52") (pin "2") (pinfunction "2_2") (pintype "input"))
      (node (ref "U18") (pin "7") (pinfunction "OUT2_7") (pintype "unspecified"))
    )
    (net (code "8") (name "/I-FB") (class "Default")
      (node (ref "H5") (pin "1") (pinfunction "1_1") (pintype "unspecified"))
      (node (ref "H5") (pin "2") (pinfunction "2_2") (pintype "unspecified"))
      (node (ref "R17") (pin "2") (pinfunction "2_2") (pintype "input"))
      (node (ref "R18") (pin "1") (pinfunction "1_1") (pintype "unspecified"))
      (node (ref "R22") (pin "1") (pinfunction "1_1") (pintype "input"))
      (node (ref "R23") (pin "2") (pinfunction "2_2") (pintype "input"))
      (node (ref "U4") (pin "5") (pinfunction "COMP_5") (pintype "unspecified"))
    )
    (net (code "9") (name "/I-VOUT") (class "Default")
      (node (ref "R25") (pin "1") (pinfunction "1_1") (pintype "input"))
      (node (ref "U5") (pin "1") (pinfunction "OUT_1") (pintype "unspecified"))
    )
    (net (code "10") (name "/IN-") (class "Default")
      (node (ref "C14") (pin "2") (pinfunction "2_2") (pintype "input"))
      (node (ref "U1") (pin "12") (pinfunction "VBUS_12") (pintype "unspecified"))
      (node (ref "U1") (pin "14") (pinfunction "IN-_14") (pintype "unspecified"))
      (node (ref "U1") (pin "15") (pinfunction "IN-_15") (pintype "unspecified"))
      (node (ref "U1") (pin "16") (pinfunction "IN-_16") (pintype "unspecified"))
      (node (ref "U13") (pin "1") (pinfunction "1_1") (pintype "unspecified"))
    )
    (net (code "11") (name "/OSCIN") (class "Default")
      (node (ref "C11") (pin "2") (pinfunction "2_2") (pintype "input"))
      (node (ref "U2") (pin "5") (pinfunction "PD0-OSC_IN_5") (pintype "unspecified"))
      (node (ref "X1") (pin "2") (pinfunction "2_2") (pintype "unspecified"))
    )
    (net (code "12") (name "/OSCOUT") (class "Default")
      (node (ref "C12") (pin "2") (pinfunction "2_2") (pintype "input"))
      (node (ref "U2") (pin "6") (pinfunction "PD1-OSC_OUT_6") (pintype "unspecified"))
      (node (ref "X1") (pin "1") (pinfunction "1_1") (pintype "unspecified"))
    )
    (net (code "13") (name "/PA0") (class "Default")
      (node (ref "H3") (pin "1") (pinfunction "1_1") (pintype "unspecified"))
      (node (ref "U2") (pin "10") (pinfunction "PA0-WKUP_10") (pintype "unspecified"))
    )
    (net (code "14") (name "/PA1") (class "Default")
      (node (ref "H3") (pin "2") (pinfunction "2_2") (pintype "unspecified"))
      (node (ref "U2") (pin "11") (pinfunction "PA1_11") (pintype "unspecified"))
    )
    (net (code "15") (name "/PA2") (class "Default")
      (node (ref "H3") (pin "3") (pinfunction "3_3") (pintype "unspecified"))
      (node (ref "U2") (pin "12") (pinfunction "PA2_12") (pintype "unspecified"))
    )
    (net (code "16") (name "/PA3") (class "Default")
      (node (ref "H3") (pin "4") (pinfunction "4_4") (pintype "unspecified"))
      (node (ref "U2") (pin "13") (pinfunction "PA3_13") (pintype "unspecified"))
    )
    (net (code "17") (name "/PA4") (class "Default")
      (node (ref "H3") (pin "5") (pinfunction "5_5") (pintype "unspecified"))
      (node (ref "U2") (pin "14") (pinfunction "PA4_14") (pintype "unspecified"))
    )
    (net (code "18") (name "/PA5") (class "Default")
      (node (ref "H3") (pin "6") (pinfunction "6_6") (pintype "unspecified"))
      (node (ref "U2") (pin "15") (pinfunction "PA5_15") (pintype "unspecified"))
    )
    (net (code "19") (name "/PA6") (class "Default")
      (node (ref "H3") (pin "7") (pinfunction "7_7") (pintype "unspecified"))
      (node (ref "U2") (pin "16") (pinfunction "PA6_16") (pintype "unspecified"))
    )
    (net (code "20") (name "/PA7") (class "Default")
      (node (ref "H3") (pin "8") (pinfunction "8_8") (pintype "unspecified"))
      (node (ref "U2") (pin "17") (pinfunction "PA7_17") (pintype "unspecified"))
    )
    (net (code "21") (name "/PA8") (class "Default")
      (node (ref "C22") (pin "1") (pinfunction "1_1") (pintype "input"))
      (node (ref "R28") (pin "1") (pinfunction "1_1") (pintype "input"))
      (node (ref "U2") (pin "29") (pinfunction "PA8_29") (pintype "unspecified"))
    )
    (net (code "22") (name "/PA9") (class "Default")
      (node (ref "C23") (pin "2") (pinfunction "2_2") (pintype "input"))
      (node (ref "R30") (pin "1") (pinfunction "1_1") (pintype "input"))
      (node (ref "U2") (pin "30") (pinfunction "PA9_30") (pintype "unspecified"))
    )
    (net (code "23") (name "/PA12") (class "Default")
      (node (ref "U2") (pin "33") (pinfunction "PA12_33") (pintype "unspecified"))
    )
    (net (code "24") (name "/PA15") (class "Default")
      (node (ref "U2") (pin "38") (pinfunction "PA15_38") (pintype "unspecified"))
    )
    (net (code "25") (name "/PB0") (class "Default")
      (node (ref "U2") (pin "18") (pinfunction "PB0_18") (pintype "unspecified"))
    )
    (net (code "26") (name "/PB1") (class "Default")
      (node (ref "U2") (pin "19") (pinfunction "PB1_19") (pintype "unspecified"))
    )
    (net (code "27") (name "/PB3") (class "Default")
      (node (ref "U2") (pin "39") (pinfunction "PB3_39") (pintype "unspecified"))
    )
    (net (code "28") (name "/PB4") (class "Default")
      (node (ref "H2") (pin "3") (pinfunction "3_3") (pintype "unspecified"))
      (node (ref "U2") (pin "40") (pinfunction "PB4_40") (pintype "unspecified"))
    )
    (net (code "29") (name "/PB5") (class "Default")
      (node (ref "H2") (pin "4") (pinfunction "4_4") (pintype "unspecified"))
      (node (ref "U2") (pin "41") (pinfunction "PB5_41") (pintype "unspecified"))
    )
    (net (code "30") (name "/PB6") (class "Default")
      (node (ref "C24") (pin "1") (pinfunction "1_1") (pintype "input"))
      (node (ref "R32") (pin "1") (pinfunction "1_1") (pintype "input"))
      (node (ref "U2") (pin "42") (pinfunction "PB6_42") (pintype "unspecified"))
    )
    (net (code "31") (name "/PB7") (class "Default")
      (node (ref "C25") (pin "2") (pinfunction "2_2") (pintype "input"))
      (node (ref "R34") (pin "1") (pinfunction "1_1") (pintype "input"))
      (node (ref "U2") (pin "43") (pinfunction "PB7_43") (pintype "unspecified"))
    )
    (net (code "32") (name "/PB8") (class "Default")
      (node (ref "C30") (pin "1") (pinfunction "1_1") (pintype "input"))
      (node (ref "R57") (pin "1") (pinfunction "1_1") (pintype "input"))
      (node (ref "SW4") (pin "1") (pinfunction "1_1") (pintype "unspecified"))
      (node (ref "U2") (pin "45") (pinfunction "PB8_45") (pintype "unspecified"))
    )
    (net (code "33") (name "/PB9") (class "Default")
      (node (ref "LED4") (pin "2") (pinfunction "A_2") (pintype "input"))
      (node (ref "U17") (pin "3") (pinfunction "EN/UVLO_3") (pintype "unspecified"))
      (node (ref "U2") (pin "46") (pinfunction "PB9_46") (pintype "unspecified"))
    )
    (net (code "34") (name "/PB10") (class "Default")
      (node (ref "R43") (pin "2") (pinfunction "2_2") (pintype "input"))
      (node (ref "U2") (pin "21") (pinfunction "PB10_21") (pintype "unspecified"))
    )
    (net (code "35") (name "/PB11") (class "Default")
      (node (ref "R44") (pin "2") (pinfunction "2_2") (pintype "input"))
      (node (ref "U2") (pin "22") (pinfunction "PB11_22") (pintype "unspecified"))
    )
    (net (code "36") (name "/PB12") (class "Default")
      (node (ref "U2") (pin "25") (pinfunction "PB12_25") (pintype "unspecified"))
    )
    (net (code "37") (name "/PB13") (class "Default")
      (node (ref "U2") (pin "26") (pinfunction "PB13_26") (pintype "unspecified"))
    )
    (net (code "38") (name "/PB14") (class "Default")
      (node (ref "U2") (pin "27") (pinfunction "PB14_27") (pintype "unspecified"))
    )
    (net (code "39") (name "/PB15") (class "Default")
      (node (ref "U2") (pin "28") (pinfunction "PB15_28") (pintype "unspecified"))
    )
    (net (code "40") (name "/PC13") (class "Default")
      (node (ref "U2") (pin "2") (pinfunction "PC13-TAMPER-RTC_2") (pintype "unspecified"))
    )
    (net (code "41") (name "/PC14") (class "Default")
      (node (ref "R61") (pin "1") (pinfunction "1_1") (pintype "input"))
      (node (ref "U2") (pin "3") (pinfunction "PC14-OSC32_IN_3") (pintype "unspecified"))
    )
    (net (code "42") (name "/PC15") (class "Default")
      (node (ref "R62") (pin "1") (pinfunction "1_1") (pintype "input"))
      (node (ref "U2") (pin "4") (pinfunction "PC15-OSC32_OUT_4") (pintype "unspecified"))
    )
    (net (code "43") (name "/PGND") (class "Default")
      (node (ref "C13") (pin "1") (pinfunction "1_1") (pintype "input"))
      (node (ref "C14") (pin "1") (pinfunction "1_1") (pintype "input"))
      (node (ref "C15") (pin "2") (pinfunction "2_2") (pintype "input"))
      (node (ref "C16") (pin "2") (pinfunction "2_2") (pintype "input"))
      (node (ref "C17") (pin "2") (pinfunction "2_2") (pintype "input"))
      (node (ref "C18") (pin "1") (pinfunction "1_1") (pintype "input"))
      (node (ref "C19") (pin "2") (pinfunction "2_2") (pintype "input"))
      (node (ref "C20") (pin "1") (pinfunction "1_1") (pintype "input"))
      (node (ref "C26") (pin "2") (pinfunction "2_2") (pintype "input"))
      (node (ref "C31") (pin "1") (pinfunction "1_1") (pintype "input"))
      (node (ref "C32") (pin "2") (pinfunction "2_2") (pintype "input"))
      (node (ref "C33") (pin "2") (pinfunction "2_2") (pintype "input"))
      (node (ref "C34") (pin "2") (pinfunction "2_2") (pintype "input"))
      (node (ref "D1") (pin "2") (pinfunction "A_2") (pintype "unspecified"))
      (node (ref "Q2") (pin "3") (pinfunction "E_3") (pintype "unspecified"))
      (node (ref "R17") (pin "1") (pinfunction "1_1") (pintype "input"))
      (node (ref "R26") (pin "2") (pinfunction "2_2") (pintype "unspecified"))
      (node (ref "R35") (pin "1") (pinfunction "1_1") (pintype "input"))
      (node (ref "R45") (pin "2") (pinfunction "2_2") (pintype "input"))
      (node (ref "R58") (pin "2") (pinfunction "2_2") (pintype "input"))
      (node (ref "U1") (pin "11") (pinfunction "GND_11") (pintype "unspecified"))
      (node (ref "U1") (pin "4") (pinfunction "A1_4") (pintype "unspecified"))
      (node (ref "U1") (pin "5") (pinfunction "A0_5") (pintype "unspecified"))
      (node (ref "U1") (pin "6") (pinfunction "GND_6") (pintype "unspecified"))
      (node (ref "U17") (pin "2") (pinfunction "GND_2") (pintype "unspecified"))
      (node (ref "U4") (pin "4") (pinfunction "GND_4") (pintype "unspecified"))
      (node (ref "U5") (pin "2") (pinfunction "GND_2") (pintype "unspecified"))
      (node (ref "U5") (pin "4") (pinfunction "IN-_4") (pintype "unspecified"))
      (node (ref "U6") (pin "4") (pinfunction "GND_4") (pintype "unspecified"))
    )
    (net (code "44") (name "/QOD") (class "Default")
      (node (ref "R59") (pin "2") (pinfunction "2_2") (pintype "input"))
      (node (ref "U17") (pin "5") (pinfunction "QOD_5") (pintype "unspecified"))
    )
    (net (code "45") (name "/RESET") (class "Default")
      (node (ref "C10") (pin "1") (pinfunction "1_1") (pintype "input"))
      (node (ref "R8") (pin "1") (pinfunction "1_1") (pintype "input"))
      (node (ref "SW1") (pin "1") (pinfunction "1_1") (pintype "unspecified"))
      (node (ref "U2") (pin "7") (pinfunction "NRST_7") (pintype "unspecified"))
    )
    (net (code "46") (name "/RS+") (class "Default")
      (node (ref "R26") (pin "1") (pinfunction "1_1") (pintype "unspecified"))
      (node (ref "U13") (pin "2") (pinfunction "2_2") (pintype "unspecified"))
      (node (ref "U5") (pin "3") (pinfunction "IN+_3") (pintype "unspecified"))
    )
    (net (code "47") (name "/SCL2") (class "Default")
      (node (ref "R41") (pin "2") (pinfunction "2_2") (pintype "input"))
      (node (ref "R43") (pin "1") (pinfunction "1_1") (pintype "input"))
      (node (ref "U1") (pin "9") (pinfunction "SCL_9") (pintype "unspecified"))
      (node (ref "U12") (pin "6") (pinfunction "SCLK/SCL_6") (pintype "unspecified"))
      (node (ref "U8") (pin "6") (pinfunction "SCLK/SCL_6") (pintype "unspecified"))
    )
    (net (code "48") (name "/SDA2") (class "Default")
      (node (ref "R42") (pin "2") (pinfunction "2_2") (pintype "input"))
      (node (ref "R44") (pin "1") (pinfunction "1_1") (pintype "input"))
      (node (ref "U1") (pin "8") (pinfunction "SDA_8") (pintype "unspecified"))
      (node (ref "U12") (pin "8") (pinfunction "SDIN/SDA_8") (pintype "unspecified"))
      (node (ref "U8") (pin "8") (pinfunction "SDIN/SDA_8") (pintype "unspecified"))
    )
    (net (code "49") (name "/STEP-DOWN1") (class "Default")
      (node (ref "Q1") (pin "2") (pinfunction "C_2") (pintype "unspecified"))
      (node (ref "R15") (pin "2") (pinfunction "2_2") (pintype "input"))
      (node (ref "U4") (pin "1") (pinfunction "SWC_1") (pintype "unspecified"))
      (node (ref "U4") (pin "7") (pinfunction "IPK_7") (pintype "unspecified"))
      (node (ref "U4") (pin "8") (pinfunction "DRC_8") (pintype "unspecified"))
    )
    (net (code "50") (name "/SWCLK") (class "Default")
      (node (ref "R7") (pin "2") (pinfunction "2_2") (pintype "input"))
      (node (ref "U2") (pin "37") (pinfunction "PA14_37") (pintype "unspecified"))
      (node (ref "U3") (pin "3") (pinfunction "3_3") (pintype "unspecified"))
    )
    (net (code "51") (name "/SWDIO") (class "Default")
      (node (ref "R6") (pin "2") (pinfunction "2_2") (pintype "input"))
      (node (ref "U2") (pin "34") (pinfunction "PA13_34") (pintype "unspecified"))
      (node (ref "U3") (pin "2") (pinfunction "2_2") (pintype "unspecified"))
    )
    (net (code "52") (name "/V-UP") (class "Default")
      (node (ref "C15") (pin "1") (pinfunction "1_1") (pintype "input"))
      (node (ref "C26") (pin "1") (pinfunction "1_1") (pintype "input"))
      (node (ref "D3") (pin "1") (pinfunction "K_1") (pintype "unspecified"))
      (node (ref "H4") (pin "1") (pinfunction "1_1") (pintype "unspecified"))
      (node (ref "H4") (pin "2") (pinfunction "2_2") (pintype "unspecified"))
      (node (ref "R15") (pin "1") (pinfunction "1_1") (pintype "input"))
      (node (ref "R36") (pin "2") (pinfunction "2_2") (pintype "unspecified"))
      (node (ref "U18") (pin "4") (pinfunction "VCC+_4") (pintype "unspecified"))
      (node (ref "U4") (pin "6") (pinfunction "VCC_6") (pintype "unspecified"))
    )
    (net (code "53") (name "/VBAT") (class "Default")
      (node (ref "U2") (pin "1") (pinfunction "VBAT_1") (pintype "unspecified"))
    )
    (net (code "54") (name "/VOUT") (class "Default")
      (node (ref "C16") (pin "1") (pinfunction "1_1") (pintype "input"))
      (node (ref "H6") (pin "1") (pinfunction "1_1") (pintype "unspecified"))
      (node (ref "H6") (pin "2") (pinfunction "2_2") (pintype "unspecified"))
      (node (ref "L1") (pin "1") (pinfunction "1_1") (pintype "unspecified"))
      (node (ref "L3") (pin "1") (pinfunction "1_1") (pintype "unspecified"))
      (node (ref "R18") (pin "2") (pinfunction "2_2") (pintype "unspecified"))
    )
    (net (code "55") (name "/VOUT-FILTER") (class "Default")
      (node (ref "C34") (pin "1") (pinfunction "1_1") (pintype "input"))
      (node (ref "L3") (pin "2") (pinfunction "2_2") (pintype "unspecified"))
      (node (ref "U1") (pin "1") (pinfunction "IN+_1") (pintype "unspecified"))
      (node (ref "U1") (pin "2") (pinfunction "IN+_2") (pintype "unspecified"))
      (node (ref "U1") (pin "3") (pinfunction "IN+_3") (pintype "unspecified"))
    )
    (net (code "56") (name "GND") (class "Default")
      (node (ref "C1") (pin "1") (pinfunction "1_1") (pintype "input"))
      (node (ref "C10") (pin "2") (pinfunction "2_2") (pintype "input"))
      (node (ref "C11") (pin "1") (pinfunction "1_1") (pintype "input"))
      (node (ref "C12") (pin "1") (pinfunction "1_1") (pintype "input"))
      (node (ref "C2") (pin "1") (pinfunction "1_1") (pintype "input"))
      (node (ref "C21") (pin "1") (pinfunction "1_1") (pintype "input"))
      (node (ref "C22") (pin "2") (pinfunction "2_2") (pintype "input"))
      (node (ref "C23") (pin "1") (pinfunction "1_1") (pintype "input"))
      (node (ref "C24") (pin "2") (pinfunction "2_2") (pintype "input"))
      (node (ref "C25") (pin "1") (pinfunction "1_1") (pintype "input"))
      (node (ref "C27") (pin "1") (pinfunction "1_1") (pintype "input"))
      (node (ref "C28") (pin "1") (pinfunction "1_1") (pintype "input"))
      (node (ref "C29") (pin "1") (pinfunction "1_1") (pintype "input"))
      (node (ref "C3") (pin "1") (pinfunction "1_1") (pintype "input"))
      (node (ref "C30") (pin "2") (pinfunction "2_2") (pintype "input"))
      (node (ref "C35") (pin "2") (pinfunction "2_2") (pintype "input"))
      (node (ref "C36") (pin "2") (pinfunction "2_2") (pintype "input"))
      (node (ref "C4") (pin "1") (pinfunction "1_1") (pintype "input"))
      (node (ref "C5") (pin "1") (pinfunction "1_1") (pintype "input"))
      (node (ref "C6") (pin "1") (pinfunction "1_1") (pintype "input"))
      (node (ref "C7") (pin "1") (pinfunction "1_1") (pintype "input"))
      (node (ref "C8") (pin "1") (pinfunction "1_1") (pintype "input"))
      (node (ref "H1") (pin "5") (pinfunction "5_5") (pintype "input"))
      (node (ref "H1") (pin "6") (pinfunction "6_6") (pintype "input"))
      (node (ref "H2") (pin "1") (pinfunction "1_1") (pintype "unspecified"))
      (node (ref "H8") (pin "1") (pinfunction "1_1") (pintype "unspecified"))
      (node (ref "H8") (pin "2") (pinfunction "2_2") (pintype "unspecified"))
      (node (ref "H9") (pin "1") (pinfunction "1_1") (pintype "unspecified"))
      (node (ref "H9") (pin "2") (pinfunction "2_2") (pintype "unspecified"))
      (node (ref "LDO1") (pin "2") (pinfunction "VSS_2") (pintype "unspecified"))
      (node (ref "R1") (pin "2") (pinfunction "2_2") (pintype "input"))
      (node (ref "R10") (pin "2") (pinfunction "2_2") (pintype "input"))
      (node (ref "R2") (pin "2") (pinfunction "2_2") (pintype "input"))
      (node (ref "R39") (pin "2") (pinfunction "2_2") (pintype "input"))
      (node (ref "R40") (pin "2") (pinfunction "2_2") (pintype "input"))
      (node (ref "R54") (pin "2") (pinfunction "2_2") (pintype "input"))
      (node (ref "R58") (pin "1") (pinfunction "1_1") (pintype "input"))
      (node (ref "R60") (pin "1") (pinfunction "1_1") (pintype "input"))
      (node (ref "R7") (pin "1") (pinfunction "1_1") (pintype "input"))
      (node (ref "SW1") (pin "2") (pinfunction "2_2") (pintype "unspecified"))
      (node (ref "SW2") (pin "C") (pinfunction "C_C") (pintype "unspecified"))
      (node (ref "SW2") (pin "D") (pinfunction "D_D") (pintype "unspecified"))
      (node (ref "SW2") (pin "EH") (pinfunction "EH_EH") (pintype "unspecified"))
      (node (ref "SW3") (pin "C") (pinfunction "C_C") (pintype "unspecified"))
      (node (ref "SW3") (pin "D") (pinfunction "D_D") (pintype "unspecified"))
      (node (ref "SW3") (pin "EH") (pinfunction "EH_EH") (pintype "unspecified"))
      (node (ref "SW4") (pin "2") (pinfunction "2_2") (pintype "unspecified"))
      (node (ref "U12") (pin "4") (pinfunction "AGND_4") (pintype "unspecified"))
      (node (ref "U18") (pin "11") (pinfunction "VCC-_11") (pintype "unspecified"))
      (node (ref "U2") (pin "23") (pinfunction "VSS_1_23") (pintype "unspecified"))
      (node (ref "U2") (pin "35") (pinfunction "VSS_2_35") (pintype "unspecified"))
      (node (ref "U2") (pin "47") (pinfunction "VSS_3_47") (pintype "unspecified"))
      (node (ref "U2") (pin "8") (pinfunction "VSSA_8") (pintype "unspecified"))
      (node (ref "U3") (pin "4") (pinfunction "4_4") (pintype "unspecified"))
      (node (ref "U8") (pin "4") (pinfunction "AGND_4") (pintype "unspecified"))
      (node (ref "U8") (pin "7") (pinfunction "SYNC#/A0_7") (pintype "unspecified"))
      (node (ref "USB1") (pin "1") (pinfunction "1_1") (pintype "unspecified"))
      (node (ref "USB1") (pin "2") (pinfunction "2_2") (pintype "unspecified"))
      (node (ref "USB1") (pin "3") (pinfunction "3_3") (pintype "unspecified"))
      (node (ref "USB1") (pin "4") (pinfunction "4_4") (pintype "unspecified"))
      (node (ref "USB1") (pin "A12") (pinfunction "GND_A12") (pintype "unspecified"))
      (node (ref "USB1") (pin "B12") (pinfunction "GND_B12") (pintype "unspecified"))
    )
    (net (code "57") (name "Net-(C35-Pad1)") (class "Default")
      (node (ref "C35") (pin "1") (pinfunction "1_1") (pintype "input"))
      (node (ref "R55") (pin "1") (pinfunction "1_1") (pintype "input"))
      (node (ref "R61") (pin "2") (pinfunction "2_2") (pintype "input"))
      (node (ref "SW2") (pin "E") (pinfunction "E_E") (pintype "unspecified"))
    )
    (net (code "58") (name "Net-(C36-Pad1)") (class "Default")
      (node (ref "C36") (pin "1") (pinfunction "1_1") (pintype "input"))
      (node (ref "R56") (pin "2") (pinfunction "2_2") (pintype "input"))
      (node (ref "R62") (pin "2") (pinfunction "2_2") (pintype "input"))
      (node (ref "SW3") (pin "E") (pinfunction "E_E") (pintype "unspecified"))
    )
    (net (code "59") (name "Net-(D1-K)") (class "Default")
      (node (ref "D1") (pin "1") (pinfunction "K_1") (pintype "unspecified"))
      (node (ref "L1") (pin "2") (pinfunction "2_2") (pintype "unspecified"))
      (node (ref "Q1") (pin "3") (pinfunction "E_3") (pintype "unspecified"))
      (node (ref "R37") (pin "1") (pinfunction "1_1") (pintype "input"))
    )
    (net (code "60") (name "Net-(D2-A)") (class "Default")
      (node (ref "D2") (pin "1") (pinfunction "A_1") (pintype "unspecified"))
      (node (ref "R53") (pin "2") (pinfunction "2_2") (pintype "input"))
      (node (ref "U18") (pin "1") (pinfunction "OUT1_1") (pintype "unspecified"))
    )
    (net (code "61") (name "Net-(D2-K)") (class "Default")
      (node (ref "D2") (pin "2") (pinfunction "K_2") (pintype "unspecified"))
      (node (ref "R22") (pin "2") (pinfunction "2_2") (pintype "input"))
    )
    (net (code "62") (name "Net-(D3-A)") (class "Default")
      (node (ref "D3") (pin "2") (pinfunction "A_2") (pintype "unspecified"))
      (node (ref "L2") (pin "1") (pinfunction "1_1") (pintype "unspecified"))
      (node (ref "Q2") (pin "2") (pinfunction "C_2") (pintype "unspecified"))
      (node (ref "U6") (pin "1") (pinfunction "SWC_1") (pintype "unspecified"))
    )
    (net (code "63") (name "Net-(H1-Pad3)") (class "Default")
      (node (ref "H1") (pin "3") (pinfunction "3_3") (pintype "input"))
      (node (ref "R5") (pin "2") (pinfunction "2_2") (pintype "input"))
    )
    (net (code "64") (name "Net-(H1-Pad4)") (class "Default")
      (node (ref "H1") (pin "4") (pinfunction "4_4") (pintype "input"))
      (node (ref "R4") (pin "1") (pinfunction "1_1") (pintype "input"))
    )
    (net (code "65") (name "Net-(LED1-C)") (class "Default")
      (node (ref "LED1") (pin "1") (pinfunction "C_1") (pintype "input"))
      (node (ref "R2") (pin "1") (pinfunction "1_1") (pintype "input"))
    )
    (net (code "66") (name "Net-(LED2-C)") (class "Default")
      (node (ref "LED2") (pin "1") (pinfunction "C_1") (pintype "input"))
      (node (ref "R39") (pin "1") (pinfunction "1_1") (pintype "input"))
    )
    (net (code "67") (name "Net-(LED3-C)") (class "Default")
      (node (ref "LED3") (pin "1") (pinfunction "C_1") (pintype "input"))
      (node (ref "R40") (pin "1") (pinfunction "1_1") (pintype "input"))
    )
    (net (code "68") (name "Net-(LED4-C)") (class "Default")
      (node (ref "LED4") (pin "1") (pinfunction "C_1") (pintype "input"))
      (node (ref "R54") (pin "1") (pinfunction "1_1") (pintype "input"))
    )
    (net (code "69") (name "Net-(Q1-B)") (class "Default")
      (node (ref "Q1") (pin "1") (pinfunction "B_1") (pintype "unspecified"))
      (node (ref "R37") (pin "2") (pinfunction "2_2") (pintype "input"))
      (node (ref "U4") (pin "2") (pinfunction "SWE_2") (pintype "unspecified"))
    )
    (net (code "70") (name "Net-(Q2-B)") (class "Default")
      (node (ref "Q2") (pin "1") (pinfunction "B_1") (pintype "unspecified"))
      (node (ref "R45") (pin "1") (pinfunction "1_1") (pintype "input"))
      (node (ref "U6") (pin "2") (pinfunction "SWE_2") (pintype "unspecified"))
    )
    (net (code "71") (name "Net-(R27-Pad1)") (class "Default")
      (node (ref "R27") (pin "1") (pinfunction "1_1") (pintype "input"))
      (node (ref "R28") (pin "2") (pinfunction "2_2") (pintype "input"))
      (node (ref "SW2") (pin "A") (pinfunction "A_A") (pintype "unspecified"))
    )
    (net (code "72") (name "Net-(R29-Pad2)") (class "Default")
      (node (ref "R29") (pin "2") (pinfunction "2_2") (pintype "input"))
      (node (ref "R30") (pin "2") (pinfunction "2_2") (pintype "input"))
      (node (ref "SW2") (pin "B") (pinfunction "B_B") (pintype "unspecified"))
    )
    (net (code "73") (name "Net-(R31-Pad1)") (class "Default")
      (node (ref "R31") (pin "1") (pinfunction "1_1") (pintype "input"))
      (node (ref "R32") (pin "2") (pinfunction "2_2") (pintype "input"))
      (node (ref "SW3") (pin "A") (pinfunction "A_A") (pintype "unspecified"))
    )
    (net (code "74") (name "Net-(R33-Pad2)") (class "Default")
      (node (ref "R33") (pin "2") (pinfunction "2_2") (pintype "input"))
      (node (ref "R34") (pin "2") (pinfunction "2_2") (pintype "input"))
      (node (ref "SW3") (pin "B") (pinfunction "B_B") (pintype "unspecified"))
    )
    (net (code "75") (name "Net-(U1-ALERT)") (class "Default")
      (node (ref "R14") (pin "2") (pinfunction "2_2") (pintype "input"))
      (node (ref "U1") (pin "7") (pinfunction "ALERT_7") (pintype "unspecified"))
    )
    (net (code "76") (name "Net-(U4-TCAP)") (class "Default")
      (node (ref "C20") (pin "2") (pinfunction "2_2") (pintype "input"))
      (node (ref "U4") (pin "3") (pinfunction "TCAP_3") (pintype "unspecified"))
    )
    (net (code "77") (name "Net-(U6-COMP)") (class "Default")
      (node (ref "R35") (pin "2") (pinfunction "2_2") (pintype "input"))
      (node (ref "R36") (pin "3") (pinfunction "3_3") (pintype "unspecified"))
      (node (ref "U6") (pin "5") (pinfunction "COMP_5") (pintype "unspecified"))
    )
    (net (code "78") (name "Net-(U6-DRC)") (class "Default")
      (node (ref "R21") (pin "1") (pinfunction "1_1") (pintype "input"))
      (node (ref "U6") (pin "8") (pinfunction "DRC_8") (pintype "unspecified"))
    )
    (net (code "79") (name "Net-(U6-IPK)") (class "Default")
      (node (ref "L2") (pin "2") (pinfunction "2_2") (pintype "unspecified"))
      (node (ref "R20") (pin "1") (pinfunction "1_1") (pintype "input"))
      (node (ref "R21") (pin "2") (pinfunction "2_2") (pintype "input"))
      (node (ref "U6") (pin "7") (pinfunction "IPK_7") (pintype "unspecified"))
    )
    (net (code "80") (name "Net-(U6-TCAP)") (class "Default")
      (node (ref "C18") (pin "2") (pinfunction "2_2") (pintype "input"))
      (node (ref "U6") (pin "3") (pinfunction "TCAP_3") (pintype "unspecified"))
    )
    (net (code "81") (name "Net-(U8-VREFIO)") (class "Default")
      (node (ref "C27") (pin "2") (pinfunction "2_2") (pintype "input"))
      (node (ref "U8") (pin "10") (pinfunction "VREFIO_10") (pintype "unspecified"))
    )
    (net (code "82") (name "Net-(U12-VREFIO)") (class "Default")
      (node (ref "C29") (pin "2") (pinfunction "2_2") (pintype "input"))
      (node (ref "U12") (pin "10") (pinfunction "VREFIO_10") (pintype "unspecified"))
    )
    (net (code "83") (name "Net-(U17-CT)") (class "Default")
      (node (ref "C32") (pin "1") (pinfunction "1_1") (pintype "input"))
      (node (ref "U17") (pin "4") (pinfunction "CT_4") (pintype "unspecified"))
    )
    (net (code "84") (name "Net-(U18A-IN1+)") (class "Default")
      (node (ref "R25") (pin "2") (pinfunction "2_2") (pintype "input"))
      (node (ref "U18") (pin "3") (pinfunction "IN1+_3") (pintype "unspecified"))
    )
    (net (code "85") (name "Net-(U18A-IN1-)") (class "Default")
      (node (ref "R24") (pin "2") (pinfunction "2_2") (pintype "input"))
      (node (ref "R53") (pin "1") (pinfunction "1_1") (pintype "input"))
      (node (ref "U18") (pin "2") (pinfunction "IN1-_2") (pintype "unspecified"))
    )
    (net (code "86") (name "Net-(U18B-IN2+)") (class "Default")
      (node (ref "R51") (pin "2") (pinfunction "2_2") (pintype "input"))
      (node (ref "U18") (pin "5") (pinfunction "IN2+_5") (pintype "unspecified"))
    )
    (net (code "87") (name "Net-(U18B-IN2-)") (class "Default")
      (node (ref "R52") (pin "1") (pinfunction "1_1") (pintype "input"))
      (node (ref "R60") (pin "2") (pinfunction "2_2") (pintype "input"))
      (node (ref "U18") (pin "6") (pinfunction "IN2-_6") (pintype "unspecified"))
    )
    (net (code "88") (name "Net-(USB1-CC1)") (class "Default")
      (node (ref "R1") (pin "1") (pinfunction "1_1") (pintype "input"))
      (node (ref "USB1") (pin "A5") (pinfunction "CC1_A5") (pintype "unspecified"))
    )
    (net (code "89") (name "Net-(USB1-CC2)") (class "Default")
      (node (ref "R10") (pin "1") (pinfunction "1_1") (pintype "input"))
      (node (ref "USB1") (pin "B5") (pinfunction "CC2_B5") (pintype "unspecified"))
    )
    (net (code "90") (name "PA10") (class "Default")
      (node (ref "LED2") (pin "2") (pinfunction "A_2") (pintype "input"))
      (node (ref "U2") (pin "31") (pinfunction "PA10_31") (pintype "unspecified"))
    )
    (net (code "91") (name "PA11") (class "Default")
      (node (ref "LED3") (pin "2") (pinfunction "A_2") (pintype "input"))
      (node (ref "U2") (pin "32") (pinfunction "PA11_32") (pintype "unspecified"))
    )
    (net (code "92") (name "VCC") (class "Default")
      (node (ref "C13") (pin "2") (pinfunction "2_2") (pintype "input"))
      (node (ref "C21") (pin "2") (pinfunction "2_2") (pintype "input"))
      (node (ref "C28") (pin "2") (pinfunction "2_2") (pintype "input"))
      (node (ref "C3") (pin "2") (pinfunction "2_2") (pintype "input"))
      (node (ref "C4") (pin "2") (pinfunction "2_2") (pintype "input"))
      (node (ref "C5") (pin "2") (pinfunction "2_2") (pintype "input"))
      (node (ref "C6") (pin "2") (pinfunction "2_2") (pintype "input"))
      (node (ref "C7") (pin "2") (pinfunction "2_2") (pintype "input"))
      (node (ref "C8") (pin "2") (pinfunction "2_2") (pintype "input"))
      (node (ref "H1") (pin "1") (pinfunction "1_1") (pintype "input"))
      (node (ref "H1") (pin "2") (pinfunction "2_2") (pintype "input"))
      (node (ref "H2") (pin "2") (pinfunction "2_2") (pintype "unspecified"))
      (node (ref "LDO1") (pin "5") (pinfunction "VOUT_5") (pintype "unspecified"))
      (node (ref "LED1") (pin "2") (pinfunction "A_2") (pintype "input"))
      (node (ref "R14") (pin "1") (pinfunction "1_1") (pintype "input"))
      (node (ref "R27") (pin "2") (pinfunction "2_2") (pintype "input"))
      (node (ref "R29") (pin "1") (pinfunction "1_1") (pintype "input"))
      (node (ref "R31") (pin "2") (pinfunction "2_2") (pintype "input"))
      (node (ref "R33") (pin "1") (pinfunction "1_1") (pintype "input"))
      (node (ref "R41") (pin "1") (pinfunction "1_1") (pintype "input"))
      (node (ref "R42") (pin "1") (pinfunction "1_1") (pintype "input"))
      (node (ref "R55") (pin "2") (pinfunction "2_2") (pintype "input"))
      (node (ref "R56") (pin "1") (pinfunction "1_1") (pintype "input"))
      (node (ref "R57") (pin "2") (pinfunction "2_2") (pintype "input"))
      (node (ref "R6") (pin "1") (pinfunction "1_1") (pintype "input"))
      (node (ref "R8") (pin "2") (pinfunction "2_2") (pintype "input"))
      (node (ref "U1") (pin "10") (pinfunction "VS_10") (pintype "unspecified"))
      (node (ref "U12") (pin "1") (pinfunction "VDD_1") (pintype "unspecified"))
      (node (ref "U12") (pin "5") (pinfunction "SPI2C_5") (pintype "unspecified"))
      (node (ref "U12") (pin "7") (pinfunction "SYNC#/A0_7") (pintype "unspecified"))
      (node (ref "U2") (pin "24") (pinfunction "VDD_1_24") (pintype "unspecified"))
      (node (ref "U2") (pin "36") (pinfunction "VDD_2_36") (pintype "unspecified"))
      (node (ref "U2") (pin "48") (pinfunction "VDD_3_48") (pintype "unspecified"))
      (node (ref "U2") (pin "9") (pinfunction "VDDA_9") (pintype "unspecified"))
      (node (ref "U3") (pin "1") (pinfunction "1_1") (pintype "unspecified"))
      (node (ref "U8") (pin "1") (pinfunction "VDD_1") (pintype "unspecified"))
      (node (ref "U8") (pin "5") (pinfunction "SPI2C_5") (pintype "unspecified"))
    )
    (net (code "93") (name "unconnected-(LDO1-NC-Pad4)") (class "Default")
      (node (ref "LDO1") (pin "4") (pinfunction "NC_4") (pintype "unspecified+no_connect"))
    )
    (net (code "94") (name "unconnected-(R18-Pad3)") (class "Default")
      (node (ref "R18") (pin "3") (pinfunction "3_3") (pintype "unspecified"))
    )
    (net (code "95") (name "unconnected-(R36-Pad1)") (class "Default")
      (node (ref "R36") (pin "1") (pinfunction "1_1") (pintype "unspecified"))
    )
    (net (code "96") (name "unconnected-(U1-NC-Pad13)") (class "Default")
      (node (ref "U1") (pin "13") (pinfunction "NC_13") (pintype "unspecified+no_connect"))
    )
    (net (code "97") (name "unconnected-(U8-NC-Pad3)") (class "Default")
      (node (ref "U8") (pin "3") (pinfunction "NC_3") (pintype "unspecified+no_connect"))
    )
    (net (code "98") (name "unconnected-(U8-NC-Pad9)") (class "Default")
      (node (ref "U8") (pin "9") (pinfunction "NC_9") (pintype "unspecified+no_connect"))
    )
    (net (code "99") (name "unconnected-(U12-NC-Pad3)") (class "Default")
      (node (ref "U12") (pin "3") (pinfunction "NC_3") (pintype "unspecified+no_connect"))
    )
    (net (code "100") (name "unconnected-(U12-NC-Pad9)") (class "Default")
      (node (ref "U12") (pin "9") (pinfunction "NC_9") (pintype "unspecified+no_connect"))
    )
  )
)
